# motor.net
KiCad netlist of a schematic drawn in Altium Designer
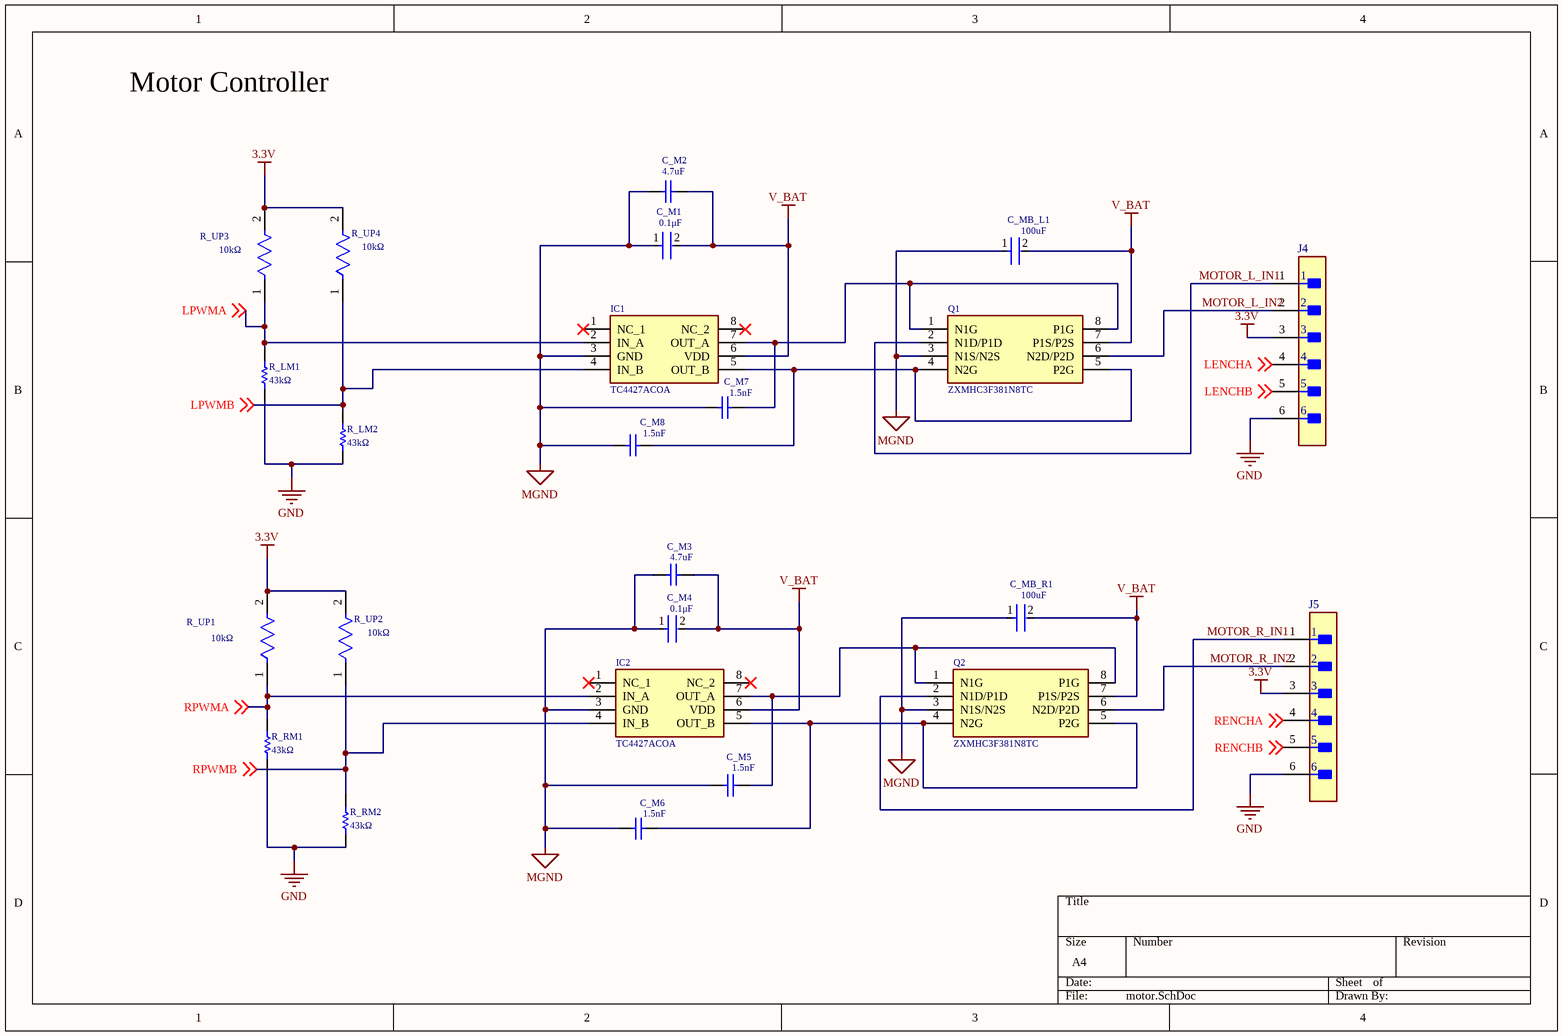
[diagram p0: motor.SchDoc]

(export (version "E")
  (design (tool "Eeschema 10.0.6"))
  (components
    (comp (ref "C_M1")
      (value "0.1μF")
      (footprint "FP-C0805C-DN-MFG")
      (description "CAP CER 0.1UF 10V 5% X7R 0805")
      (fields (field (name "MANUFACTURER") "KEMET") (field (name "TOLERANCE") "0.05"))
      (libsource (lib "Altium Content Vault") (part "b4654b650e69147ec39a6b967a45e02"))
    )
    (comp (ref "C_M2")
      (value "4.7uF")
      (footprint "CAPC2013X145X50NL20T25")
      (fields (field (name "PART NUMBER") "C0805C475M3PACTU") (field (name "MANUFACTURER") "Kemet"))
      (libsource (lib "Altium Content Vault") (part "CAP"))
    )
    (comp (ref "C_M3")
      (value "4.7uF")
      (footprint "CAPC2013X145X50NL20T25")
      (fields (field (name "PART NUMBER") "C0805C475M3PACTU") (field (name "MANUFACTURER") "Kemet"))
      (libsource (lib "Altium Content Vault") (part "CAP"))
    )
    (comp (ref "C_M4")
      (value "0.1μF")
      (footprint "FP-C0805C-DN-MFG")
      (description "CAP CER 0.1UF 10V 5% X7R 0805")
      (fields (field (name "MANUFACTURER") "KEMET") (field (name "TOLERANCE") "0.05"))
      (libsource (lib "Altium Content Vault") (part "b4654b650e69147ec39a6b967a45e02"))
    )
    (comp (ref "C_M5")
      (value "08051C152KAT2A")
      (footprint "CAPC2013X94X50ML20T25")
      (fields (field (name "MANUFACTURER") "AVX Interconnect / Elco") (field (name "CAPACITANCE") "1.5nF"))
      (libsource (lib "Altium Content Vault") (part "CAP"))
    )
    (comp (ref "C_M6")
      (value "08051C152KAT2A")
      (footprint "CAPC2013X94X50ML20T25")
      (fields (field (name "MANUFACTURER") "AVX Interconnect / Elco") (field (name "CAPACITANCE") "1.5nF"))
      (libsource (lib "Altium Content Vault") (part "CAP"))
    )
    (comp (ref "C_M7")
      (value "08051C152KAT2A")
      (footprint "CAPC2013X94X50ML20T25")
      (fields (field (name "MANUFACTURER") "AVX Interconnect / Elco") (field (name "CAPACITANCE") "1.5nF"))
      (libsource (lib "Altium Content Vault") (part "CAP"))
    )
    (comp (ref "C_M8")
      (value "08051C152KAT2A")
      (footprint "CAPC2013X94X50ML20T25")
      (fields (field (name "MANUFACTURER") "AVX Interconnect / Elco") (field (name "CAPACITANCE") "1.5nF"))
      (libsource (lib "Altium Content Vault") (part "CAP"))
    )
    (comp (ref "C_MB_L1")
      (value "100uF")
      (footprint "FP-C1206C-EH-MFG")
      (description "CAP CER 100UF 6.3V X5R 1206")
      (fields (field (name "TOLERANCE") "2%") (field (name "VOLTAGE") "6.3V"))
      (libsource (lib "Altium Content Vault") (part "02cd4be3c70576c341d710602a673aa"))
    )
    (comp (ref "C_MB_R1")
      (value "100uF")
      (footprint "FP-C1206C-EH-MFG")
      (description "CAP CER 100UF 6.3V X5R 1206")
      (fields (field (name "TOLERANCE") "2%") (field (name "VOLTAGE") "6.3V"))
      (libsource (lib "Altium Content Vault") (part "02cd4be3c70576c341d710602a673aa"))
    )
    (comp (ref "IC1")
      (value "TC4427ACOA")
      (footprint "SamacSys:SOIC127P600X175-8N")
      (description "Integrated Circuit")
      (fields (field (name "MOUSER PART NUMBER") "579-TC4427ACOA"))
      (libsource (lib "*") (part "TC4427ACOA"))
    )
    (comp (ref "IC2")
      (value "TC4427ACOA")
      (footprint "SamacSys:SOIC127P600X175-8N")
      (description "Integrated Circuit")
      (fields (field (name "MOUSER PART NUMBER") "579-TC4427ACOA"))
      (libsource (lib "*") (part "TC4427ACOA"))
    )
    (comp (ref "J4")
      (value "22-28-4063")
      (footprint "FP-22-28-4063-MFG")
      (description "CONN HEADER VERT 6POS 2.54MM")
      (libsource (lib "Altium Content Vault") (part "f2cb566baf1c37ab5a3b8e90bbeafd6"))
    )
    (comp (ref "J5")
      (value "22-28-4063")
      (footprint "FP-22-28-4063-MFG")
      (description "CONN HEADER VERT 6POS 2.54MM")
      (libsource (lib "Altium Content Vault") (part "f2cb566baf1c37ab5a3b8e90bbeafd6"))
    )
    (comp (ref "Q1")
      (value "ZXMHC3F381N8TC")
      (footprint "SamacSys:SOIC127P600X175-8N")
      (description "MOSFET (N-Channel)")
      (fields (field (name "MOUSER PART NUMBER") "522-ZXMHC3F381N8TC"))
      (libsource (lib "*") (part "ZXMHC3F381N8TC"))
    )
    (comp (ref "Q2")
      (value "ZXMHC3F381N8TC")
      (footprint "SamacSys:SOIC127P600X175-8N")
      (description "MOSFET (N-Channel)")
      (fields (field (name "MOUSER PART NUMBER") "522-ZXMHC3F381N8TC"))
      (libsource (lib "*") (part "ZXMHC3F381N8TC"))
    )
    (comp (ref "R_LM1")
      (value "43kΩ")
      (footprint "RESC1608X55X30NL20T20")
      (fields (field (name "PART NUMBER") "ERA3AEB433V") (field (name "MANUFACTURER") "Panasonic"))
      (libsource (lib "Altium Content Vault") (part "RES"))
    )
    (comp (ref "R_LM2")
      (value "43kΩ")
      (footprint "RESC1608X55X30NL20T20")
      (fields (field (name "PART NUMBER") "ERA3AEB433V") (field (name "MANUFACTURER") "Panasonic"))
      (libsource (lib "Altium Content Vault") (part "RES"))
    )
    (comp (ref "R_RM1")
      (value "43kΩ")
      (footprint "RESC1608X55X30NL20T20")
      (fields (field (name "PART NUMBER") "ERA3AEB433V") (field (name "MANUFACTURER") "Panasonic"))
      (libsource (lib "Altium Content Vault") (part "RES"))
    )
    (comp (ref "R_RM2")
      (value "43kΩ")
      (footprint "RESC1608X55X30NL20T20")
      (fields (field (name "PART NUMBER") "ERA3AEB433V") (field (name "MANUFACTURER") "Panasonic"))
      (libsource (lib "Altium Content Vault") (part "RES"))
    )
    (comp (ref "R_UP1")
      (value "10kΩ")
      (footprint "FP-ERA3A-IPC_C")
      (description "RES SMD 10K OHM 0.1% 1/10W 0603")
      (fields (field (name "TOLERANCE") "0.1%") (field (name "Comment") "ERA-3AEB103V"))
      (libsource (lib "Altium Content Vault") (part "4e5f8b3dd332802e91518312df5df73"))
    )
    (comp (ref "R_UP2")
      (value "10kΩ")
      (footprint "FP-ERA3A-IPC_C")
      (description "RES SMD 10K OHM 0.1% 1/10W 0603")
      (fields (field (name "TOLERANCE") "0.1%") (field (name "Comment") "ERA-3AEB103V"))
      (libsource (lib "Altium Content Vault") (part "4e5f8b3dd332802e91518312df5df73"))
    )
    (comp (ref "R_UP3")
      (value "10kΩ")
      (footprint "FP-ERA3A-IPC_C")
      (description "RES SMD 10K OHM 0.1% 1/10W 0603")
      (fields (field (name "TOLERANCE") "0.1%") (field (name "Comment") "ERA-3AEB103V"))
      (libsource (lib "Altium Content Vault") (part "4e5f8b3dd332802e91518312df5df73"))
    )
    (comp (ref "R_UP4")
      (value "10kΩ")
      (footprint "FP-ERA3A-IPC_C")
      (description "RES SMD 10K OHM 0.1% 1/10W 0603")
      (fields (field (name "TOLERANCE") "0.1%") (field (name "Comment") "ERA-3AEB103V"))
      (libsource (lib "Altium Content Vault") (part "4e5f8b3dd332802e91518312df5df73"))
    )
  )
  (nets
    (net (code "1") (name "/MOTOR_L_IN1") (class "Default")
      (node (ref "J4") (pin "1") (pinfunction "1_1") (pintype "passive"))
      (node (ref "Q1") (pin "2") (pinfunction "N1D/P1D_2") (pintype "passive"))
    )
    (net (code "2") (name "/MOTOR_L_IN2") (class "Default")
      (node (ref "J4") (pin "2") (pinfunction "2_2") (pintype "passive"))
      (node (ref "Q1") (pin "6") (pinfunction "N2D/P2D_6") (pintype "passive"))
    )
    (net (code "3") (name "/MOTOR_R_IN1") (class "Default")
      (node (ref "J5") (pin "1") (pinfunction "1_1") (pintype "passive"))
      (node (ref "Q2") (pin "2") (pinfunction "N1D/P1D_2") (pintype "passive"))
    )
    (net (code "4") (name "/MOTOR_R_IN2") (class "Default")
      (node (ref "J5") (pin "2") (pinfunction "2_2") (pintype "passive"))
      (node (ref "Q2") (pin "6") (pinfunction "N2D/P2D_6") (pintype "passive"))
    )
    (net (code "5") (name "3.3V") (class "Default")
      (node (ref "J4") (pin "3") (pinfunction "3_3") (pintype "passive"))
      (node (ref "J5") (pin "3") (pinfunction "3_3") (pintype "passive"))
      (node (ref "R_UP1") (pin "2") (pinfunction "2_2") (pintype "passive"))
      (node (ref "R_UP2") (pin "2") (pinfunction "2_2") (pintype "passive"))
      (node (ref "R_UP3") (pin "2") (pinfunction "2_2") (pintype "passive"))
      (node (ref "R_UP4") (pin "2") (pinfunction "2_2") (pintype "passive"))
    )
    (net (code "6") (name "GND") (class "Default")
      (node (ref "J4") (pin "6") (pinfunction "6_6") (pintype "passive"))
      (node (ref "J5") (pin "6") (pinfunction "6_6") (pintype "passive"))
      (node (ref "R_LM1") (pin "1") (pinfunction "1_1") (pintype "passive"))
      (node (ref "R_LM2") (pin "1") (pinfunction "1_1") (pintype "passive"))
      (node (ref "R_RM1") (pin "1") (pinfunction "1_1") (pintype "passive"))
      (node (ref "R_RM2") (pin "1") (pinfunction "1_1") (pintype "passive"))
    )
    (net (code "7") (name "LENCHA") (class "Default")
      (node (ref "J4") (pin "4") (pinfunction "4_4") (pintype "passive"))
    )
    (net (code "8") (name "LENCHB") (class "Default")
      (node (ref "J4") (pin "5") (pinfunction "5_5") (pintype "passive"))
    )
    (net (code "9") (name "LPWMA") (class "Default")
      (node (ref "IC1") (pin "2") (pinfunction "IN_A_2") (pintype "passive"))
      (node (ref "R_LM1") (pin "2") (pinfunction "2_2") (pintype "passive"))
      (node (ref "R_UP3") (pin "1") (pinfunction "1_1") (pintype "passive"))
    )
    (net (code "10") (name "LPWMB") (class "Default")
      (node (ref "IC1") (pin "4") (pinfunction "IN_B_4") (pintype "passive"))
      (node (ref "R_LM2") (pin "2") (pinfunction "2_2") (pintype "passive"))
      (node (ref "R_UP4") (pin "1") (pinfunction "1_1") (pintype "passive"))
    )
    (net (code "11") (name "MGND") (class "Default")
      (node (ref "C_M1") (pin "1") (pinfunction "1_1") (pintype "passive"))
      (node (ref "C_M2") (pin "2") (pinfunction "2_2") (pintype "passive"))
      (node (ref "C_M3") (pin "2") (pinfunction "2_2") (pintype "passive"))
      (node (ref "C_M4") (pin "1") (pinfunction "1_1") (pintype "passive"))
      (node (ref "C_M5") (pin "2") (pinfunction "2_2") (pintype "passive"))
      (node (ref "C_M6") (pin "2") (pinfunction "2_2") (pintype "passive"))
      (node (ref "C_M7") (pin "2") (pinfunction "2_2") (pintype "passive"))
      (node (ref "C_M8") (pin "2") (pinfunction "2_2") (pintype "passive"))
      (node (ref "C_MB_L1") (pin "1") (pinfunction "1_1") (pintype "passive"))
      (node (ref "C_MB_R1") (pin "1") (pinfunction "1_1") (pintype "passive"))
      (node (ref "IC1") (pin "3") (pinfunction "GND_3") (pintype "passive"))
      (node (ref "IC2") (pin "3") (pinfunction "GND_3") (pintype "passive"))
      (node (ref "Q1") (pin "3") (pinfunction "N1S/N2S_3") (pintype "passive"))
      (node (ref "Q2") (pin "3") (pinfunction "N1S/N2S_3") (pintype "passive"))
    )
    (net (code "12") (name "Net-(IC1-OUT_A)") (class "Default")
      (node (ref "C_M7") (pin "1") (pinfunction "1_1") (pintype "passive"))
      (node (ref "IC1") (pin "7") (pinfunction "OUT_A_7") (pintype "passive"))
      (node (ref "Q1") (pin "1") (pinfunction "N1G_1") (pintype "passive"))
      (node (ref "Q1") (pin "8") (pinfunction "P1G_8") (pintype "passive"))
    )
    (net (code "13") (name "Net-(IC1-OUT_B)") (class "Default")
      (node (ref "C_M8") (pin "1") (pinfunction "1_1") (pintype "passive"))
      (node (ref "IC1") (pin "5") (pinfunction "OUT_B_5") (pintype "passive"))
      (node (ref "Q1") (pin "4") (pinfunction "N2G_4") (pintype "passive"))
      (node (ref "Q1") (pin "5") (pinfunction "P2G_5") (pintype "passive"))
    )
    (net (code "14") (name "Net-(IC2-OUT_A)") (class "Default")
      (node (ref "C_M5") (pin "1") (pinfunction "1_1") (pintype "passive"))
      (node (ref "IC2") (pin "7") (pinfunction "OUT_A_7") (pintype "passive"))
      (node (ref "Q2") (pin "1") (pinfunction "N1G_1") (pintype "passive"))
      (node (ref "Q2") (pin "8") (pinfunction "P1G_8") (pintype "passive"))
    )
    (net (code "15") (name "Net-(IC2-OUT_B)") (class "Default")
      (node (ref "C_M6") (pin "1") (pinfunction "1_1") (pintype "passive"))
      (node (ref "IC2") (pin "5") (pinfunction "OUT_B_5") (pintype "passive"))
      (node (ref "Q2") (pin "4") (pinfunction "N2G_4") (pintype "passive"))
      (node (ref "Q2") (pin "5") (pinfunction "P2G_5") (pintype "passive"))
    )
    (net (code "16") (name "RENCHA") (class "Default")
      (node (ref "J5") (pin "4") (pinfunction "4_4") (pintype "passive"))
    )
    (net (code "17") (name "RENCHB") (class "Default")
      (node (ref "J5") (pin "5") (pinfunction "5_5") (pintype "passive"))
    )
    (net (code "18") (name "RPWMA") (class "Default")
      (node (ref "IC2") (pin "2") (pinfunction "IN_A_2") (pintype "passive"))
      (node (ref "R_RM1") (pin "2") (pinfunction "2_2") (pintype "passive"))
      (node (ref "R_UP1") (pin "1") (pinfunction "1_1") (pintype "passive"))
    )
    (net (code "19") (name "RPWMB") (class "Default")
      (node (ref "IC2") (pin "4") (pinfunction "IN_B_4") (pintype "passive"))
      (node (ref "R_RM2") (pin "2") (pinfunction "2_2") (pintype "passive"))
      (node (ref "R_UP2") (pin "1") (pinfunction "1_1") (pintype "passive"))
    )
    (net (code "20") (name "V_BAT") (class "Default")
      (node (ref "C_M1") (pin "2") (pinfunction "2_2") (pintype "passive"))
      (node (ref "C_M2") (pin "1") (pinfunction "1_1") (pintype "passive"))
      (node (ref "C_M3") (pin "1") (pinfunction "1_1") (pintype "passive"))
      (node (ref "C_M4") (pin "2") (pinfunction "2_2") (pintype "passive"))
      (node (ref "C_MB_L1") (pin "2") (pinfunction "2_2") (pintype "passive"))
      (node (ref "C_MB_R1") (pin "2") (pinfunction "2_2") (pintype "passive"))
      (node (ref "IC1") (pin "6") (pinfunction "VDD_6") (pintype "passive"))
      (node (ref "IC2") (pin "6") (pinfunction "VDD_6") (pintype "passive"))
      (node (ref "Q1") (pin "7") (pinfunction "P1S/P2S_7") (pintype "passive"))
      (node (ref "Q2") (pin "7") (pinfunction "P1S/P2S_7") (pintype "passive"))
    )
    (net (code "21") (name "unconnected-(IC1-NC_1-Pad1)") (class "Default")
      (node (ref "IC1") (pin "1") (pinfunction "NC_1_1") (pintype "passive+no_connect"))
    )
    (net (code "22") (name "unconnected-(IC1-NC_2-Pad8)") (class "Default")
      (node (ref "IC1") (pin "8") (pinfunction "NC_2_8") (pintype "passive+no_connect"))
    )
    (net (code "23") (name "unconnected-(IC2-NC_1-Pad1)") (class "Default")
      (node (ref "IC2") (pin "1") (pinfunction "NC_1_1") (pintype "passive+no_connect"))
    )
    (net (code "24") (name "unconnected-(IC2-NC_2-Pad8)") (class "Default")
      (node (ref "IC2") (pin "8") (pinfunction "NC_2_8") (pintype "passive+no_connect"))
    )
  )
)
